# SCH_STAYAW_0_3_2024-05-22.net
KiCad netlist of a schematic drawn in EasyEDA
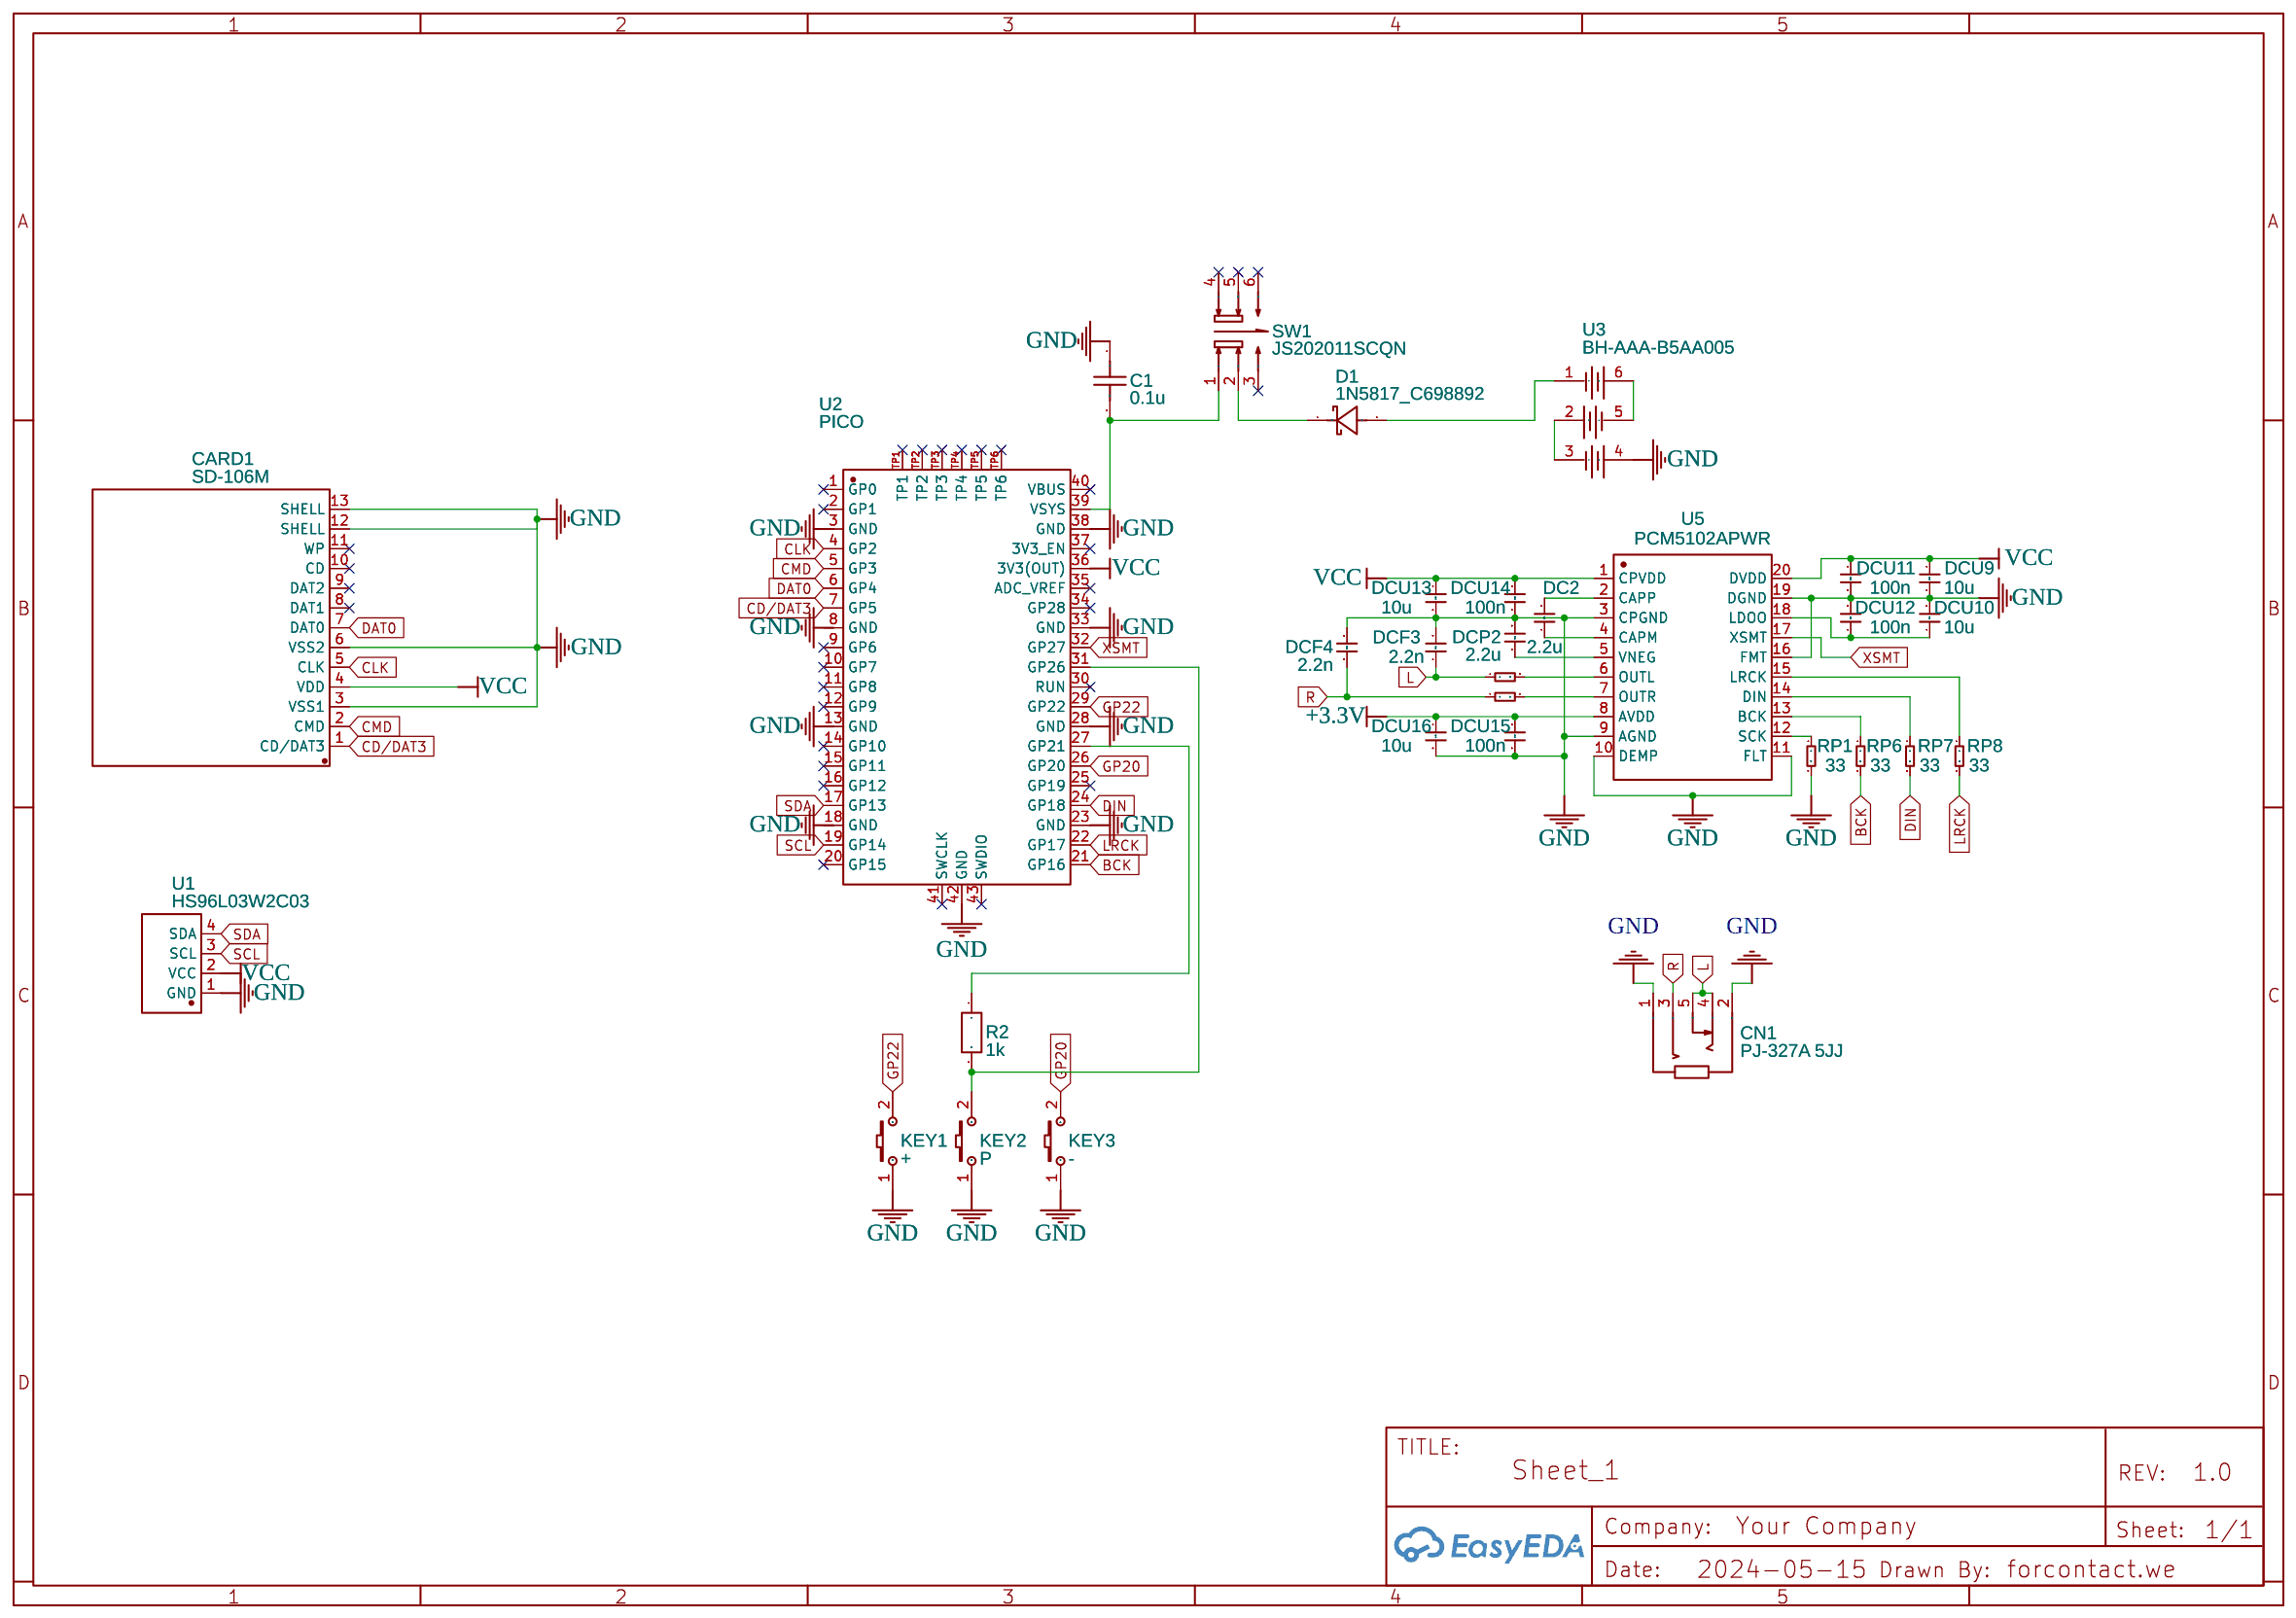
[diagram p0: schematic sheet]

(export (version "E")
  (design (tool "Eeschema 10.0.6"))
  (components
    (comp (ref "C1") (value "0.1u") (libsource (lib "") (part "C_0603_US")))
    (comp (ref "CARD1")
      (value "SD-106M")
      (fields (field (name "Manufacturer") "XUNPU(讯普)"))
      (libsource (lib "") (part "SD-106M"))
    )
    (comp (ref "CN1")
      (value "PJ-327A 5JJ")
      (fields (field (name "Manufacturer") "SHOU HAN(首韩)"))
      (libsource (lib "") (part "PJ-327A 5JJ"))
    )
    (comp (ref "D1")
      (value "1N5817_C698892")
      (fields (field (name "Manufacturer Part") "1N5817") (field (name "Manufacturer") "YANGJIE(扬杰)"))
      (libsource (lib "") (part "1N5817_C698892"))
    )
    (comp (ref "DC2")
      (value "2.2u")
      (fields (field (name "Manufacturer Part") "CL21B105KBFNNNE") (field (name "Manufacturer") "SAMSUNG"))
      (libsource (lib "") (part "Cap_0603_US_2"))
    )
    (comp (ref "DCF3")
      (value "2.2n")
      (fields (field (name "Manufacturer Part") "CL21A106KAYNNNE") (field (name "Manufacturer") "SAMSUNG"))
      (libsource (lib "") (part "Cap_0603_US_3"))
    )
    (comp (ref "DCF4")
      (value "2.2n")
      (fields (field (name "Manufacturer Part") "CL21A106KAYNNNE") (field (name "Manufacturer") "SAMSUNG"))
      (libsource (lib "") (part "Cap_0603_US_3"))
    )
    (comp (ref "DCP2")
      (value "2.2u")
      (fields (field (name "Manufacturer Part") "CL21B105KBFNNNE") (field (name "Manufacturer") "SAMSUNG"))
      (libsource (lib "") (part "Cap_0603_US_4"))
    )
    (comp (ref "DCU9")
      (value "10u")
      (fields (field (name "Manufacturer Part") "CL21A106KAYNNNE") (field (name "Manufacturer") "SAMSUNG"))
      (libsource (lib "") (part "Cap_0603_US"))
    )
    (comp (ref "DCU10")
      (value "10u")
      (fields (field (name "Manufacturer Part") "CL21A106KAYNNNE") (field (name "Manufacturer") "SAMSUNG"))
      (libsource (lib "") (part "Cap_0603_US"))
    )
    (comp (ref "DCU11")
      (value "100n")
      (fields (field (name "Manufacturer Part") "CL21A106KAYNNNE") (field (name "Manufacturer") "SAMSUNG"))
      (libsource (lib "") (part "Cap_0603_US"))
    )
    (comp (ref "DCU12")
      (value "100n")
      (fields (field (name "Manufacturer Part") "CL21A106KAYNNNE") (field (name "Manufacturer") "SAMSUNG"))
      (libsource (lib "") (part "Cap_0603_US"))
    )
    (comp (ref "DCU13")
      (value "10u")
      (fields (field (name "Manufacturer Part") "CL21A106KAYNNNE") (field (name "Manufacturer") "SAMSUNG"))
      (libsource (lib "") (part "Cap_0603_US_1"))
    )
    (comp (ref "DCU14")
      (value "100n")
      (fields (field (name "Manufacturer Part") "CL21A106KAYNNNE") (field (name "Manufacturer") "SAMSUNG"))
      (libsource (lib "") (part "Cap_0603_US_1"))
    )
    (comp (ref "DCU15")
      (value "100n")
      (fields (field (name "Manufacturer Part") "CL21A106KAYNNNE") (field (name "Manufacturer") "SAMSUNG"))
      (libsource (lib "") (part "Cap_0603_US_1"))
    )
    (comp (ref "DCU16")
      (value "10u")
      (fields (field (name "Manufacturer Part") "CL21A106KAYNNNE") (field (name "Manufacturer") "SAMSUNG"))
      (libsource (lib "") (part "Cap_0603_US_1"))
    )
    (comp (ref "DR3")
      (value "470")
      (fields (field (name "Manufacturer Part") "?"))
      (libsource (lib "") (part "Res_0603(1/10W)_EU_1"))
    )
    (comp (ref "DR4")
      (value "470")
      (fields (field (name "Manufacturer Part") "?"))
      (libsource (lib "") (part "Res_0603(1/10W)_EU_1"))
    )
    (comp (ref "KEY1")
      (value "+")
      (fields (field (name "Manufacturer Part") "K2-1107ST-A4SW-06"))
      (libsource (lib "") (part "K2-3.6×6.1_SMD"))
    )
    (comp (ref "KEY2")
      (value "P")
      (fields (field (name "Manufacturer Part") "K2-1107ST-A4SW-06"))
      (libsource (lib "") (part "K2-3.6×6.1_SMD"))
    )
    (comp (ref "KEY3")
      (value "-")
      (fields (field (name "Manufacturer Part") "K2-1107ST-A4SW-06"))
      (libsource (lib "") (part "K2-3.6×6.1_SMD"))
    )
    (comp (ref "R2") (value "1k") (libsource (lib "") (part "R_0603_EU")))
    (comp (ref "RP1")
      (value "33")
      (fields (field (name "Manufacturer Part") "?"))
      (libsource (lib "") (part "Res_0603(1/10W)_EU"))
    )
    (comp (ref "RP6")
      (value "33")
      (fields (field (name "Manufacturer Part") "?"))
      (libsource (lib "") (part "Res_0603(1/10W)_EU"))
    )
    (comp (ref "RP7")
      (value "33")
      (fields (field (name "Manufacturer Part") "?"))
      (libsource (lib "") (part "Res_0603(1/10W)_EU"))
    )
    (comp (ref "RP8")
      (value "33")
      (fields (field (name "Manufacturer Part") "?"))
      (libsource (lib "") (part "Res_0603(1/10W)_EU"))
    )
    (comp (ref "SW1")
      (value "JS202011SCQN")
      (fields (field (name "Manufacturer") "C&K"))
      (libsource (lib "") (part "JS202011SCQN"))
    )
    (comp (ref "U1")
      (value "HS96L03W2C03")
      (fields (field (name "Manufacturer") "HS(汉昇)"))
      (libsource (lib "") (part "HS96L03W2C03"))
    )
    (comp (ref "U2")
      (value "PICO")
      (fields (field (name "Manufacturer") "Raspberry Pi(树莓派)"))
      (libsource (lib "") (part "PICO"))
    )
    (comp (ref "U3")
      (value "BH-AAA-B5AA005")
      (fields (field (name "Manufacturer") "MYOUNG(美阳)"))
      (libsource (lib "") (part "BH-AAA-B5AA005"))
    )
    (comp (ref "U5")
      (value "PCM5102APWR")
      (fields (field (name "Manufacturer") "TI"))
      (libsource (lib "") (part "PCM5102APWR"))
    )
  )
  (nets
    (net (code "1") (name "+3.3V") (class "Default")
      (node (ref "DCU15") (pin "1") (pinfunction "1_1") (pintype "unspecified"))
      (node (ref "DCU16") (pin "1") (pinfunction "1_1") (pintype "unspecified"))
      (node (ref "U5") (pin "8") (pinfunction "AVDD_8") (pintype "unspecified"))
    )
    (net (code "2") (name "BCK") (class "Default")
      (node (ref "RP6") (pin "2") (pinfunction "2_2") (pintype "unspecified"))
      (node (ref "U2") (pin "21") (pinfunction "GP16_21") (pintype "unspecified"))
    )
    (net (code "3") (name "CD{slash}DAT3") (class "Default")
      (node (ref "CARD1") (pin "1") (pinfunction "CD/DAT3_1") (pintype "unspecified"))
      (node (ref "U2") (pin "7") (pinfunction "GP5_7") (pintype "unspecified"))
    )
    (net (code "4") (name "CLK") (class "Default")
      (node (ref "CARD1") (pin "5") (pinfunction "CLK_5") (pintype "unspecified"))
      (node (ref "U2") (pin "4") (pinfunction "GP2_4") (pintype "unspecified"))
    )
    (net (code "5") (name "CMD") (class "Default")
      (node (ref "CARD1") (pin "2") (pinfunction "CMD_2") (pintype "unspecified"))
      (node (ref "U2") (pin "5") (pinfunction "GP3_5") (pintype "unspecified"))
    )
    (net (code "6") (name "DAT0") (class "Default")
      (node (ref "CARD1") (pin "7") (pinfunction "DAT0_7") (pintype "unspecified"))
      (node (ref "U2") (pin "6") (pinfunction "GP4_6") (pintype "unspecified"))
    )
    (net (code "7") (name "DIN") (class "Default")
      (node (ref "RP7") (pin "2") (pinfunction "2_2") (pintype "unspecified"))
      (node (ref "U2") (pin "24") (pinfunction "GP18_24") (pintype "unspecified"))
    )
    (net (code "8") (name "GND") (class "Default")
      (node (ref "C1") (pin "1") (pinfunction "1_1") (pintype "unspecified"))
      (node (ref "CARD1") (pin "12") (pinfunction "SHELL_12") (pintype "unspecified"))
      (node (ref "CARD1") (pin "13") (pinfunction "SHELL_13") (pintype "unspecified"))
      (node (ref "CARD1") (pin "3") (pinfunction "VSS1_3") (pintype "unspecified"))
      (node (ref "CARD1") (pin "6") (pinfunction "VSS2_6") (pintype "unspecified"))
      (node (ref "CN1") (pin "1") (pinfunction "1_1") (pintype "unspecified"))
      (node (ref "CN1") (pin "2") (pinfunction "2_2") (pintype "unspecified"))
      (node (ref "DCF3") (pin "2") (pinfunction "2_2") (pintype "unspecified"))
      (node (ref "DCF4") (pin "2") (pinfunction "2_2") (pintype "unspecified"))
      (node (ref "DCP2") (pin "2") (pinfunction "2_2") (pintype "unspecified"))
      (node (ref "DCU10") (pin "2") (pinfunction "2_2") (pintype "unspecified"))
      (node (ref "DCU11") (pin "1") (pinfunction "1_1") (pintype "unspecified"))
      (node (ref "DCU12") (pin "2") (pinfunction "2_2") (pintype "unspecified"))
      (node (ref "DCU13") (pin "2") (pinfunction "2_2") (pintype "unspecified"))
      (node (ref "DCU14") (pin "2") (pinfunction "2_2") (pintype "unspecified"))
      (node (ref "DCU15") (pin "2") (pinfunction "2_2") (pintype "unspecified"))
      (node (ref "DCU16") (pin "2") (pinfunction "2_2") (pintype "unspecified"))
      (node (ref "DCU9") (pin "1") (pinfunction "1_1") (pintype "unspecified"))
      (node (ref "KEY1") (pin "1") (pinfunction "1_1") (pintype "unspecified"))
      (node (ref "KEY2") (pin "1") (pinfunction "1_1") (pintype "unspecified"))
      (node (ref "KEY3") (pin "1") (pinfunction "1_1") (pintype "unspecified"))
      (node (ref "RP1") (pin "2") (pinfunction "2_2") (pintype "unspecified"))
      (node (ref "U1") (pin "1") (pinfunction "GND_1") (pintype "unspecified"))
      (node (ref "U2") (pin "13") (pinfunction "GND_13") (pintype "unspecified"))
      (node (ref "U2") (pin "18") (pinfunction "GND_18") (pintype "unspecified"))
      (node (ref "U2") (pin "23") (pinfunction "GND_23") (pintype "unspecified"))
      (node (ref "U2") (pin "28") (pinfunction "GND_28") (pintype "unspecified"))
      (node (ref "U2") (pin "3") (pinfunction "GND_3") (pintype "unspecified"))
      (node (ref "U2") (pin "33") (pinfunction "GND_33") (pintype "unspecified"))
      (node (ref "U2") (pin "38") (pinfunction "GND_38") (pintype "unspecified"))
      (node (ref "U2") (pin "42") (pinfunction "GND_42") (pintype "unspecified"))
      (node (ref "U2") (pin "8") (pinfunction "GND_8") (pintype "unspecified"))
      (node (ref "U3") (pin "4") (pinfunction "+_4") (pintype "input"))
      (node (ref "U5") (pin "10") (pinfunction "DEMP_10") (pintype "unspecified"))
      (node (ref "U5") (pin "11") (pinfunction "FLT_11") (pintype "unspecified"))
      (node (ref "U5") (pin "16") (pinfunction "FMT_16") (pintype "unspecified"))
      (node (ref "U5") (pin "19") (pinfunction "DGND_19") (pintype "unspecified"))
      (node (ref "U5") (pin "3") (pinfunction "CPGND_3") (pintype "unspecified"))
      (node (ref "U5") (pin "9") (pinfunction "AGND_9") (pintype "unspecified"))
    )
    (net (code "9") (name "GP20") (class "Default")
      (node (ref "KEY3") (pin "2") (pinfunction "2_2") (pintype "unspecified"))
      (node (ref "U2") (pin "26") (pinfunction "GP20_26") (pintype "unspecified"))
    )
    (net (code "10") (name "GP22") (class "Default")
      (node (ref "KEY1") (pin "2") (pinfunction "2_2") (pintype "unspecified"))
      (node (ref "U2") (pin "29") (pinfunction "GP22_29") (pintype "unspecified"))
    )
    (net (code "11") (name "L") (class "Default")
      (node (ref "CN1") (pin "4") (pinfunction "4_4") (pintype "unspecified"))
      (node (ref "CN1") (pin "5") (pinfunction "5_5") (pintype "unspecified"))
      (node (ref "DCF3") (pin "1") (pinfunction "1_1") (pintype "unspecified"))
      (node (ref "DR4") (pin "1") (pinfunction "1_1") (pintype "unspecified"))
    )
    (net (code "12") (name "LRCK") (class "Default")
      (node (ref "RP8") (pin "2") (pinfunction "2_2") (pintype "unspecified"))
      (node (ref "U2") (pin "22") (pinfunction "GP17_22") (pintype "unspecified"))
    )
    (net (code "13") (name "Net-(D1-Pad1)") (class "Default")
      (node (ref "D1") (pin "1") (pinfunction "1_1") (pintype "unspecified"))
      (node (ref "SW1") (pin "2") (pinfunction "2_2") (pintype "unspecified"))
    )
    (net (code "14") (name "Net-(D1-Pad2)") (class "Default")
      (node (ref "D1") (pin "2") (pinfunction "2_2") (pintype "unspecified"))
      (node (ref "U3") (pin "1") (pinfunction "-_1") (pintype "input"))
    )
    (net (code "15") (name "Net-(U2-GP21)") (class "Default")
      (node (ref "R2") (pin "1") (pinfunction "1_1") (pintype "unspecified"))
      (node (ref "U2") (pin "27") (pinfunction "GP21_27") (pintype "unspecified"))
    )
    (net (code "16") (name "Net-(U2-GP26)") (class "Default")
      (node (ref "KEY2") (pin "2") (pinfunction "2_2") (pintype "unspecified"))
      (node (ref "R2") (pin "2") (pinfunction "2_2") (pintype "unspecified"))
      (node (ref "U2") (pin "31") (pinfunction "GP26_31") (pintype "unspecified"))
    )
    (net (code "17") (name "Net-(U2-VSYS)") (class "Default")
      (node (ref "C1") (pin "2") (pinfunction "2_2") (pintype "unspecified"))
      (node (ref "SW1") (pin "1") (pinfunction "1_1") (pintype "unspecified"))
      (node (ref "U2") (pin "39") (pinfunction "VSYS_39") (pintype "unspecified"))
    )
    (net (code "18") (name "Net-(U3-+-Pad2)") (class "Default")
      (node (ref "U3") (pin "2") (pinfunction "+_2") (pintype "input"))
      (node (ref "U3") (pin "3") (pinfunction "-_3") (pintype "input"))
    )
    (net (code "19") (name "Net-(U3-+-Pad6)") (class "Default")
      (node (ref "U3") (pin "5") (pinfunction "-_5") (pintype "input"))
      (node (ref "U3") (pin "6") (pinfunction "+_6") (pintype "input"))
    )
    (net (code "20") (name "Net-(U5-BCK)") (class "Default")
      (node (ref "RP6") (pin "1") (pinfunction "1_1") (pintype "unspecified"))
      (node (ref "U5") (pin "13") (pinfunction "BCK_13") (pintype "unspecified"))
    )
    (net (code "21") (name "Net-(U5-CAPM)") (class "Default")
      (node (ref "DC2") (pin "1") (pinfunction "1_1") (pintype "unspecified"))
      (node (ref "U5") (pin "4") (pinfunction "CAPM_4") (pintype "unspecified"))
    )
    (net (code "22") (name "Net-(U5-CAPP)") (class "Default")
      (node (ref "DC2") (pin "2") (pinfunction "2_2") (pintype "unspecified"))
      (node (ref "U5") (pin "2") (pinfunction "CAPP_2") (pintype "unspecified"))
    )
    (net (code "23") (name "Net-(U5-DIN)") (class "Default")
      (node (ref "RP7") (pin "1") (pinfunction "1_1") (pintype "unspecified"))
      (node (ref "U5") (pin "14") (pinfunction "DIN_14") (pintype "unspecified"))
    )
    (net (code "24") (name "Net-(U5-LDOO)") (class "Default")
      (node (ref "DCU10") (pin "1") (pinfunction "1_1") (pintype "unspecified"))
      (node (ref "DCU12") (pin "1") (pinfunction "1_1") (pintype "unspecified"))
      (node (ref "U5") (pin "18") (pinfunction "LDOO_18") (pintype "unspecified"))
    )
    (net (code "25") (name "Net-(U5-LRCK)") (class "Default")
      (node (ref "RP8") (pin "1") (pinfunction "1_1") (pintype "unspecified"))
      (node (ref "U5") (pin "15") (pinfunction "LRCK_15") (pintype "unspecified"))
    )
    (net (code "26") (name "Net-(U5-OUTL)") (class "Default")
      (node (ref "DR4") (pin "2") (pinfunction "2_2") (pintype "unspecified"))
      (node (ref "U5") (pin "6") (pinfunction "OUTL_6") (pintype "unspecified"))
    )
    (net (code "27") (name "Net-(U5-OUTR)") (class "Default")
      (node (ref "DR3") (pin "2") (pinfunction "2_2") (pintype "unspecified"))
      (node (ref "U5") (pin "7") (pinfunction "OUTR_7") (pintype "unspecified"))
    )
    (net (code "28") (name "Net-(U5-SCK)") (class "Default")
      (node (ref "RP1") (pin "1") (pinfunction "1_1") (pintype "unspecified"))
      (node (ref "U5") (pin "12") (pinfunction "SCK_12") (pintype "unspecified"))
    )
    (net (code "29") (name "Net-(U5-VNEG)") (class "Default")
      (node (ref "DCP2") (pin "1") (pinfunction "1_1") (pintype "unspecified"))
      (node (ref "U5") (pin "5") (pinfunction "VNEG_5") (pintype "unspecified"))
    )
    (net (code "30") (name "R") (class "Default")
      (node (ref "CN1") (pin "3") (pinfunction "3_3") (pintype "unspecified"))
      (node (ref "DCF4") (pin "1") (pinfunction "1_1") (pintype "unspecified"))
      (node (ref "DR3") (pin "1") (pinfunction "1_1") (pintype "unspecified"))
    )
    (net (code "31") (name "SCL") (class "Default")
      (node (ref "U1") (pin "3") (pinfunction "SCL_3") (pintype "unspecified"))
      (node (ref "U2") (pin "19") (pinfunction "GP14_19") (pintype "unspecified"))
    )
    (net (code "32") (name "SDA") (class "Default")
      (node (ref "U1") (pin "4") (pinfunction "SDA_4") (pintype "unspecified"))
      (node (ref "U2") (pin "17") (pinfunction "GP13_17") (pintype "unspecified"))
    )
    (net (code "33") (name "VCC") (class "Default")
      (node (ref "CARD1") (pin "4") (pinfunction "VDD_4") (pintype "unspecified"))
      (node (ref "DCU11") (pin "2") (pinfunction "2_2") (pintype "unspecified"))
      (node (ref "DCU13") (pin "1") (pinfunction "1_1") (pintype "unspecified"))
      (node (ref "DCU14") (pin "1") (pinfunction "1_1") (pintype "unspecified"))
      (node (ref "DCU9") (pin "2") (pinfunction "2_2") (pintype "unspecified"))
      (node (ref "U1") (pin "2") (pinfunction "VCC_2") (pintype "unspecified"))
      (node (ref "U2") (pin "36") (pinfunction "3V3(OUT)_36") (pintype "unspecified"))
      (node (ref "U5") (pin "1") (pinfunction "CPVDD_1") (pintype "unspecified"))
      (node (ref "U5") (pin "20") (pinfunction "DVDD_20") (pintype "unspecified"))
    )
    (net (code "34") (name "XSMT") (class "Default")
      (node (ref "U2") (pin "32") (pinfunction "GP27_32") (pintype "unspecified"))
      (node (ref "U5") (pin "17") (pinfunction "XSMT_17") (pintype "unspecified"))
    )
    (net (code "35") (name "unconnected-(CARD1-CD-Pad10)") (class "Default")
      (node (ref "CARD1") (pin "10") (pinfunction "CD_10") (pintype "unspecified+no_connect"))
    )
    (net (code "36") (name "unconnected-(CARD1-DAT1-Pad8)") (class "Default")
      (node (ref "CARD1") (pin "8") (pinfunction "DAT1_8") (pintype "unspecified+no_connect"))
    )
    (net (code "37") (name "unconnected-(CARD1-DAT2-Pad9)") (class "Default")
      (node (ref "CARD1") (pin "9") (pinfunction "DAT2_9") (pintype "unspecified+no_connect"))
    )
    (net (code "38") (name "unconnected-(CARD1-WP-Pad11)") (class "Default")
      (node (ref "CARD1") (pin "11") (pinfunction "WP_11") (pintype "unspecified+no_connect"))
    )
    (net (code "39") (name "unconnected-(SW1-Pad3)") (class "Default")
      (node (ref "SW1") (pin "3") (pinfunction "3_3") (pintype "unspecified+no_connect"))
    )
    (net (code "40") (name "unconnected-(SW1-Pad4)") (class "Default")
      (node (ref "SW1") (pin "4") (pinfunction "4_4") (pintype "unspecified+no_connect"))
    )
    (net (code "41") (name "unconnected-(SW1-Pad5)") (class "Default")
      (node (ref "SW1") (pin "5") (pinfunction "5_5") (pintype "unspecified+no_connect"))
    )
    (net (code "42") (name "unconnected-(SW1-Pad6)") (class "Default")
      (node (ref "SW1") (pin "6") (pinfunction "6_6") (pintype "unspecified+no_connect"))
    )
    (net (code "43") (name "unconnected-(U2-3V3_EN-Pad37)") (class "Default")
      (node (ref "U2") (pin "37") (pinfunction "3V3_EN_37") (pintype "unspecified+no_connect"))
    )
    (net (code "44") (name "unconnected-(U2-ADC_VREF-Pad35)") (class "Default")
      (node (ref "U2") (pin "35") (pinfunction "ADC_VREF_35") (pintype "unspecified+no_connect"))
    )
    (net (code "45") (name "unconnected-(U2-GP0-Pad1)") (class "Default")
      (node (ref "U2") (pin "1") (pinfunction "GP0_1") (pintype "unspecified+no_connect"))
    )
    (net (code "46") (name "unconnected-(U2-GP1-Pad2)") (class "Default")
      (node (ref "U2") (pin "2") (pinfunction "GP1_2") (pintype "unspecified+no_connect"))
    )
    (net (code "47") (name "unconnected-(U2-GP6-Pad9)") (class "Default")
      (node (ref "U2") (pin "9") (pinfunction "GP6_9") (pintype "unspecified+no_connect"))
    )
    (net (code "48") (name "unconnected-(U2-GP7-Pad10)") (class "Default")
      (node (ref "U2") (pin "10") (pinfunction "GP7_10") (pintype "unspecified+no_connect"))
    )
    (net (code "49") (name "unconnected-(U2-GP8-Pad11)") (class "Default")
      (node (ref "U2") (pin "11") (pinfunction "GP8_11") (pintype "unspecified+no_connect"))
    )
    (net (code "50") (name "unconnected-(U2-GP9-Pad12)") (class "Default")
      (node (ref "U2") (pin "12") (pinfunction "GP9_12") (pintype "unspecified+no_connect"))
    )
    (net (code "51") (name "unconnected-(U2-GP10-Pad14)") (class "Default")
      (node (ref "U2") (pin "14") (pinfunction "GP10_14") (pintype "unspecified+no_connect"))
    )
    (net (code "52") (name "unconnected-(U2-GP11-Pad15)") (class "Default")
      (node (ref "U2") (pin "15") (pinfunction "GP11_15") (pintype "unspecified+no_connect"))
    )
    (net (code "53") (name "unconnected-(U2-GP12-Pad16)") (class "Default")
      (node (ref "U2") (pin "16") (pinfunction "GP12_16") (pintype "unspecified+no_connect"))
    )
    (net (code "54") (name "unconnected-(U2-GP15-Pad20)") (class "Default")
      (node (ref "U2") (pin "20") (pinfunction "GP15_20") (pintype "unspecified+no_connect"))
    )
    (net (code "55") (name "unconnected-(U2-GP19-Pad25)") (class "Default")
      (node (ref "U2") (pin "25") (pinfunction "GP19_25") (pintype "unspecified+no_connect"))
    )
    (net (code "56") (name "unconnected-(U2-GP28-Pad34)") (class "Default")
      (node (ref "U2") (pin "34") (pinfunction "GP28_34") (pintype "unspecified+no_connect"))
    )
    (net (code "57") (name "unconnected-(U2-PadTP1)") (class "Default")
      (node (ref "U2") (pin "TP1") (pinfunction "TP1_TP1") (pintype "unspecified+no_connect"))
    )
    (net (code "58") (name "unconnected-(U2-PadTP2)") (class "Default")
      (node (ref "U2") (pin "TP2") (pinfunction "TP2_TP2") (pintype "unspecified+no_connect"))
    )
    (net (code "59") (name "unconnected-(U2-PadTP3)") (class "Default")
      (node (ref "U2") (pin "TP3") (pinfunction "TP3_TP3") (pintype "unspecified+no_connect"))
    )
    (net (code "60") (name "unconnected-(U2-PadTP4)") (class "Default")
      (node (ref "U2") (pin "TP4") (pinfunction "TP4_TP4") (pintype "unspecified+no_connect"))
    )
    (net (code "61") (name "unconnected-(U2-PadTP5)") (class "Default")
      (node (ref "U2") (pin "TP5") (pinfunction "TP5_TP5") (pintype "unspecified+no_connect"))
    )
    (net (code "62") (name "unconnected-(U2-PadTP6)") (class "Default")
      (node (ref "U2") (pin "TP6") (pinfunction "TP6_TP6") (pintype "unspecified+no_connect"))
    )
    (net (code "63") (name "unconnected-(U2-RUN-Pad30)") (class "Default")
      (node (ref "U2") (pin "30") (pinfunction "RUN_30") (pintype "unspecified+no_connect"))
    )
    (net (code "64") (name "unconnected-(U2-SWCLK-Pad41)") (class "Default")
      (node (ref "U2") (pin "41") (pinfunction "SWCLK_41") (pintype "unspecified+no_connect"))
    )
    (net (code "65") (name "unconnected-(U2-SWDIO-Pad43)") (class "Default")
      (node (ref "U2") (pin "43") (pinfunction "SWDIO_43") (pintype "unspecified+no_connect"))
    )
    (net (code "66") (name "unconnected-(U2-VBUS-Pad40)") (class "Default")
      (node (ref "U2") (pin "40") (pinfunction "VBUS_40") (pintype "unspecified+no_connect"))
    )
  )
)
